# moth_v3_80mm_main_board.net
KiCad netlist of a schematic drawn in EAGLE
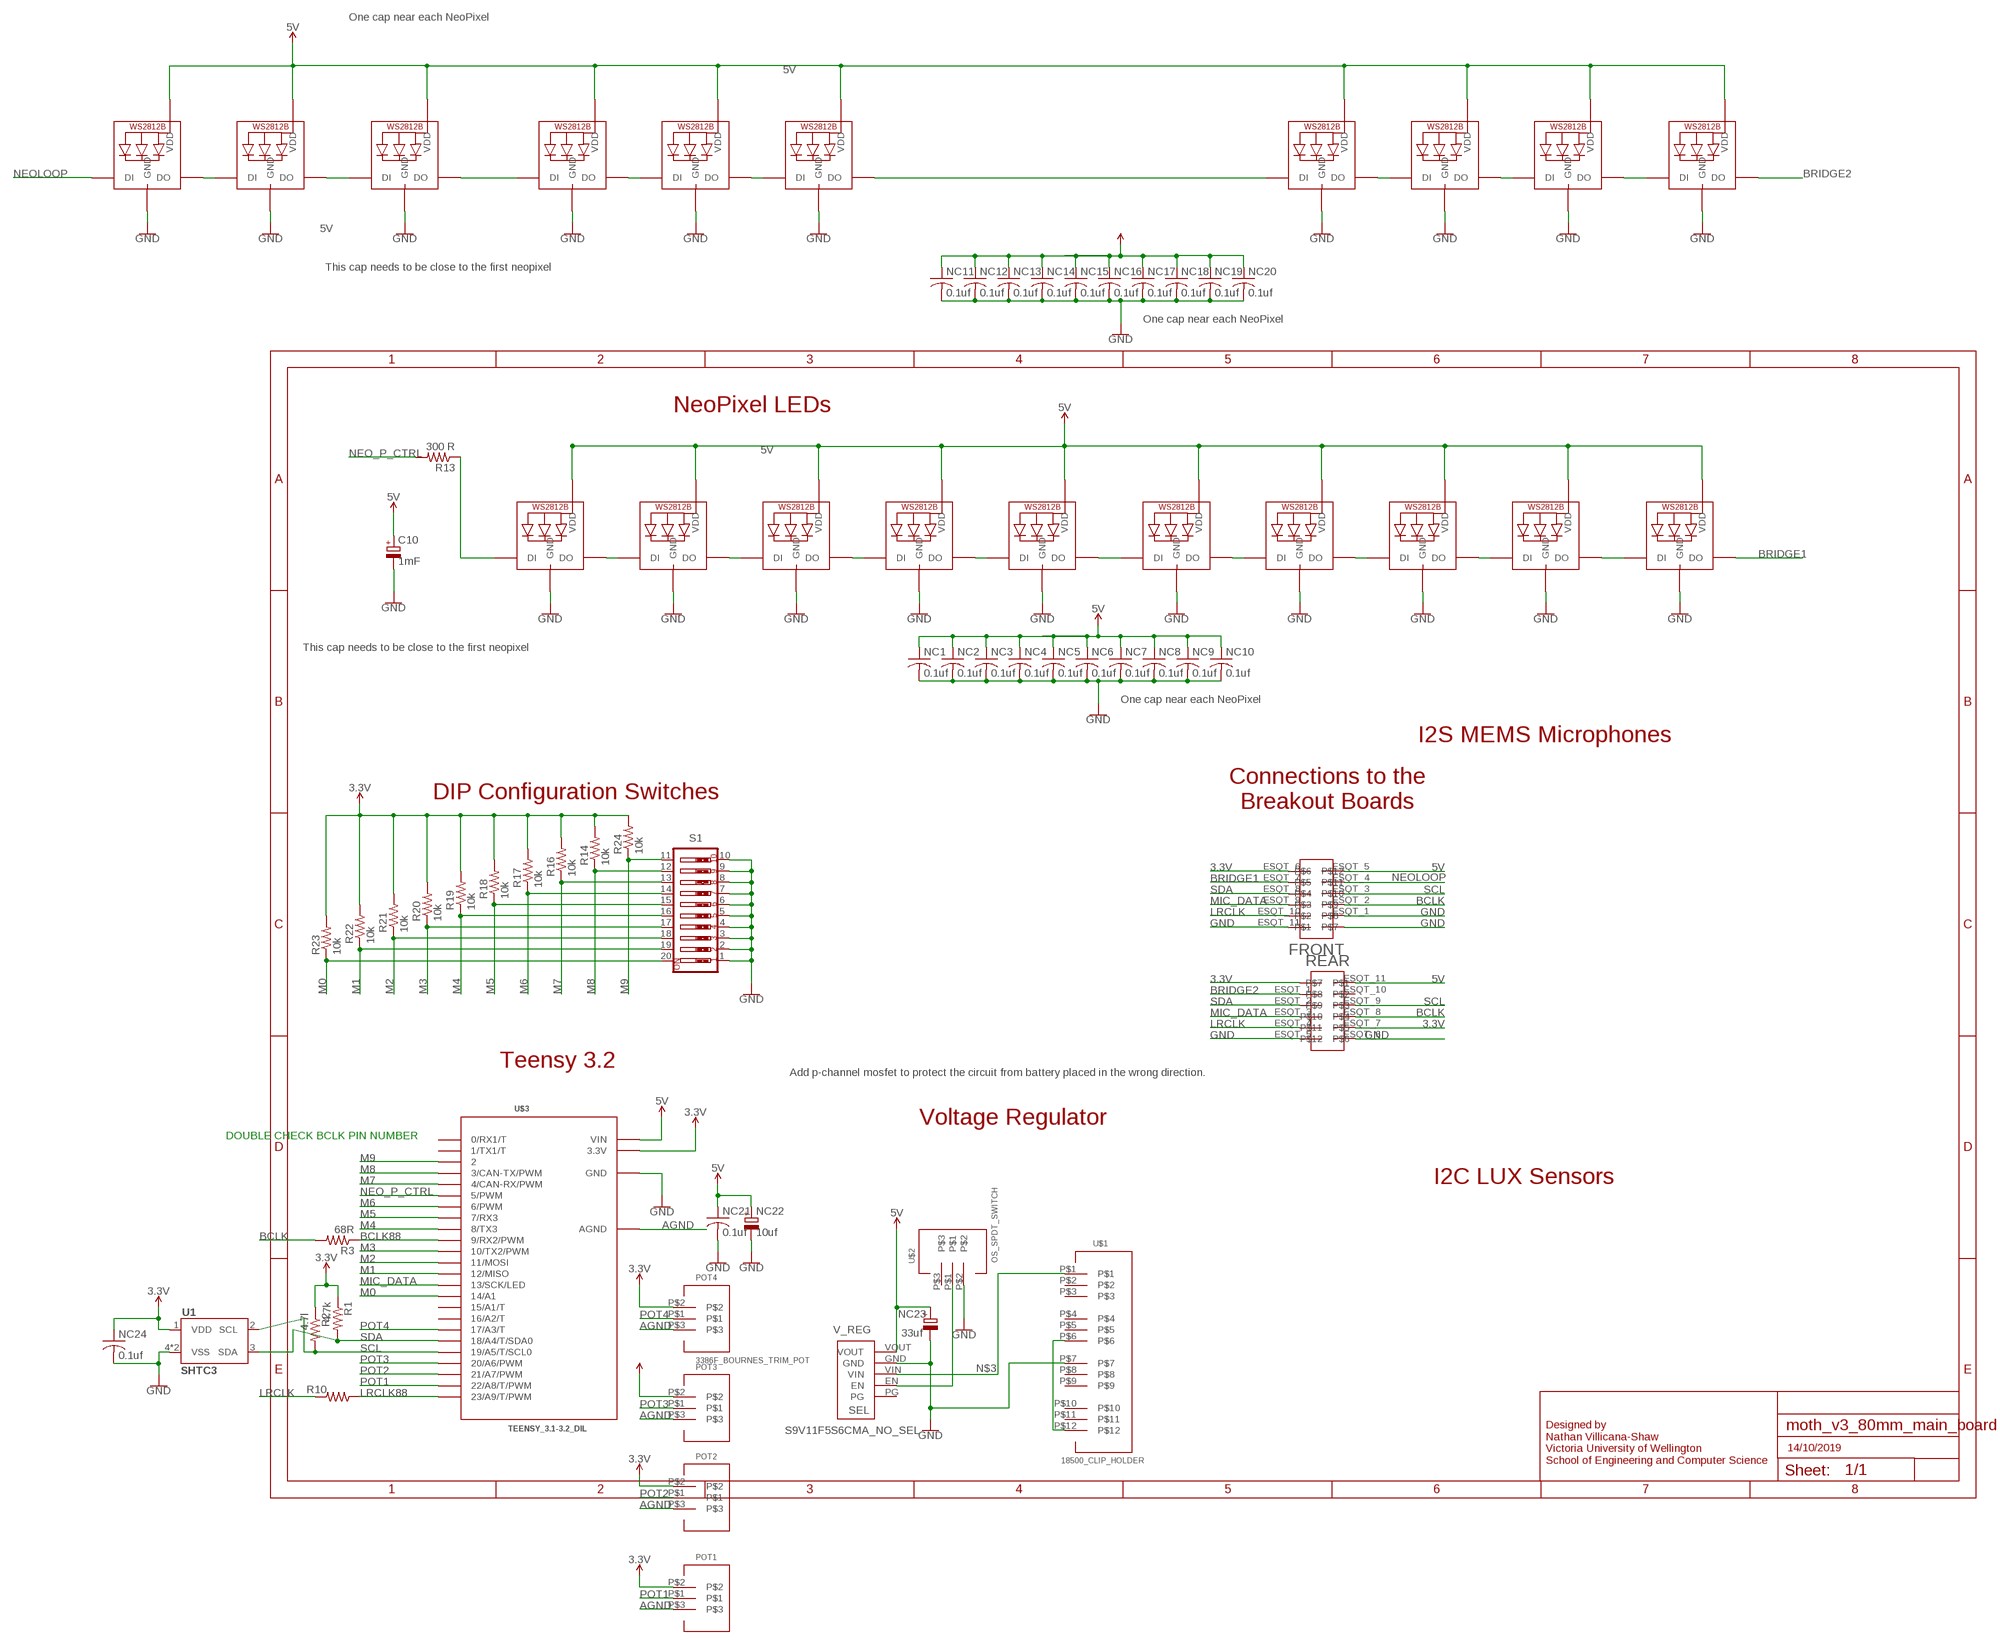
[diagram p0: schematic, sheet 1]

(export (version "E")
  (design (tool "Eeschema 10.0.6"))
  (components
    (comp (ref "C10")
      (value "1mF")
      (footprint "eagle-import:153CLV-1010")
      (libsource (lib "eagle-import") (part "CPOL-EU153CLV-1010"))
    )
    (comp (ref "FRONT")
      (value "SAMTEC_ESQT_2X6_THROUGH_HOLE")
      (footprint "eagle-import:SAMTEC_ESQT_2X6_THROUGH_HOLE")
      (libsource (lib "eagle-import") (part "SAMTEC_ESQT_2X6_THROUGH_HOLE"))
    )
    (comp (ref "NC1")
      (value "0.1uf")
      (footprint "eagle-import:C0805K")
      (libsource (lib "eagle-import") (part "C-USC0805K"))
    )
    (comp (ref "NC2")
      (value "0.1uf")
      (footprint "eagle-import:C0805K")
      (libsource (lib "eagle-import") (part "C-USC0805K"))
    )
    (comp (ref "NC3")
      (value "0.1uf")
      (footprint "eagle-import:C0805K")
      (libsource (lib "eagle-import") (part "C-USC0805K"))
    )
    (comp (ref "NC4")
      (value "0.1uf")
      (footprint "eagle-import:C0805K")
      (libsource (lib "eagle-import") (part "C-USC0805K"))
    )
    (comp (ref "NC5")
      (value "0.1uf")
      (footprint "eagle-import:C0805K")
      (libsource (lib "eagle-import") (part "C-USC0805K"))
    )
    (comp (ref "NC6")
      (value "0.1uf")
      (footprint "eagle-import:C0805K")
      (libsource (lib "eagle-import") (part "C-USC0805K"))
    )
    (comp (ref "NC7")
      (value "0.1uf")
      (footprint "eagle-import:C0805K")
      (libsource (lib "eagle-import") (part "C-USC0805K"))
    )
    (comp (ref "NC8")
      (value "0.1uf")
      (footprint "eagle-import:C0805K")
      (libsource (lib "eagle-import") (part "C-USC0805K"))
    )
    (comp (ref "NC9")
      (value "0.1uf")
      (footprint "eagle-import:C0805K")
      (libsource (lib "eagle-import") (part "C-USC0805K"))
    )
    (comp (ref "NC10")
      (value "0.1uf")
      (footprint "eagle-import:C0805K")
      (libsource (lib "eagle-import") (part "C-USC0805K"))
    )
    (comp (ref "NC11")
      (value "0.1uf")
      (footprint "eagle-import:C0805K")
      (libsource (lib "eagle-import") (part "C-USC0805K"))
    )
    (comp (ref "NC12")
      (value "0.1uf")
      (footprint "eagle-import:C0805K")
      (libsource (lib "eagle-import") (part "C-USC0805K"))
    )
    (comp (ref "NC13")
      (value "0.1uf")
      (footprint "eagle-import:C0805K")
      (libsource (lib "eagle-import") (part "C-USC0805K"))
    )
    (comp (ref "NC14")
      (value "0.1uf")
      (footprint "eagle-import:C0805K")
      (libsource (lib "eagle-import") (part "C-USC0805K"))
    )
    (comp (ref "NC15")
      (value "0.1uf")
      (footprint "eagle-import:C0805K")
      (libsource (lib "eagle-import") (part "C-USC0805K"))
    )
    (comp (ref "NC16")
      (value "0.1uf")
      (footprint "eagle-import:C0805K")
      (libsource (lib "eagle-import") (part "C-USC0805K"))
    )
    (comp (ref "NC17")
      (value "0.1uf")
      (footprint "eagle-import:C0805K")
      (libsource (lib "eagle-import") (part "C-USC0805K"))
    )
    (comp (ref "NC18")
      (value "0.1uf")
      (footprint "eagle-import:C0805K")
      (libsource (lib "eagle-import") (part "C-USC0805K"))
    )
    (comp (ref "NC19")
      (value "0.1uf")
      (footprint "eagle-import:C0805K")
      (libsource (lib "eagle-import") (part "C-USC0805K"))
    )
    (comp (ref "NC20")
      (value "0.1uf")
      (footprint "eagle-import:C0805K")
      (libsource (lib "eagle-import") (part "C-USC0805K"))
    )
    (comp (ref "NC21")
      (value "0.1uf")
      (footprint "eagle-import:C0805K")
      (libsource (lib "eagle-import") (part "C-USC0805K"))
    )
    (comp (ref "NC22")
      (value "10uf")
      (footprint "eagle-import:E2,5-7")
      (libsource (lib "eagle-import") (part "CPOL-EUE2.5-7"))
    )
    (comp (ref "NC23")
      (value "33uf")
      (footprint "eagle-import:E2,5-7")
      (libsource (lib "eagle-import") (part "CPOL-EUE2.5-7"))
    )
    (comp (ref "NC24")
      (value "0.1uf")
      (footprint "eagle-import:C0805K")
      (libsource (lib "eagle-import") (part "C-USC0805K"))
    )
    (comp (ref "NEO1")
      (value "WS2812B5050")
      (footprint "eagle-import:WS2812B")
      (libsource (lib "eagle-import") (part "WS2812B5050"))
    )
    (comp (ref "NEO2")
      (value "WS2812B5050")
      (footprint "eagle-import:WS2812B")
      (libsource (lib "eagle-import") (part "WS2812B5050"))
    )
    (comp (ref "NEO3")
      (value "WS2812B5050")
      (footprint "eagle-import:WS2812B")
      (libsource (lib "eagle-import") (part "WS2812B5050"))
    )
    (comp (ref "NEO4")
      (value "WS2812B5050")
      (footprint "eagle-import:WS2812B")
      (libsource (lib "eagle-import") (part "WS2812B5050"))
    )
    (comp (ref "NEO5")
      (value "WS2812B5050")
      (footprint "eagle-import:WS2812B")
      (libsource (lib "eagle-import") (part "WS2812B5050"))
    )
    (comp (ref "NEO6")
      (value "WS2812B5050")
      (footprint "eagle-import:WS2812B")
      (libsource (lib "eagle-import") (part "WS2812B5050"))
    )
    (comp (ref "NEO7")
      (value "WS2812B5050")
      (footprint "eagle-import:WS2812B")
      (libsource (lib "eagle-import") (part "WS2812B5050"))
    )
    (comp (ref "NEO8")
      (value "WS2812B5050")
      (footprint "eagle-import:WS2812B")
      (libsource (lib "eagle-import") (part "WS2812B5050"))
    )
    (comp (ref "NEO9")
      (value "WS2812B5050")
      (footprint "eagle-import:WS2812B")
      (libsource (lib "eagle-import") (part "WS2812B5050"))
    )
    (comp (ref "NEO10")
      (value "WS2812B5050")
      (footprint "eagle-import:WS2812B")
      (libsource (lib "eagle-import") (part "WS2812B5050"))
    )
    (comp (ref "NEO11")
      (value "WS2812B5050")
      (footprint "eagle-import:WS2812B")
      (libsource (lib "eagle-import") (part "WS2812B5050"))
    )
    (comp (ref "NEO12")
      (value "WS2812B5050")
      (footprint "eagle-import:WS2812B")
      (libsource (lib "eagle-import") (part "WS2812B5050"))
    )
    (comp (ref "NEO13")
      (value "WS2812B5050")
      (footprint "eagle-import:WS2812B")
      (libsource (lib "eagle-import") (part "WS2812B5050"))
    )
    (comp (ref "NEO14")
      (value "WS2812B5050")
      (footprint "eagle-import:WS2812B")
      (libsource (lib "eagle-import") (part "WS2812B5050"))
    )
    (comp (ref "NEO15")
      (value "WS2812B5050")
      (footprint "eagle-import:WS2812B")
      (libsource (lib "eagle-import") (part "WS2812B5050"))
    )
    (comp (ref "NEO16")
      (value "WS2812B5050")
      (footprint "eagle-import:WS2812B")
      (libsource (lib "eagle-import") (part "WS2812B5050"))
    )
    (comp (ref "NEO17")
      (value "WS2812B5050")
      (footprint "eagle-import:WS2812B")
      (libsource (lib "eagle-import") (part "WS2812B5050"))
    )
    (comp (ref "NEO18")
      (value "WS2812B5050")
      (footprint "eagle-import:WS2812B")
      (libsource (lib "eagle-import") (part "WS2812B5050"))
    )
    (comp (ref "NEO19")
      (value "WS2812B5050")
      (footprint "eagle-import:WS2812B")
      (libsource (lib "eagle-import") (part "WS2812B5050"))
    )
    (comp (ref "NEO20")
      (value "WS2812B5050")
      (footprint "eagle-import:WS2812B")
      (libsource (lib "eagle-import") (part "WS2812B5050"))
    )
    (comp (ref "POT1")
      (value "3386F_BOURNES_TRIM_POT")
      (footprint "eagle-import:3386_BOURNS_TRIM_POT")
      (libsource (lib "eagle-import") (part "3386F_BOURNES_TRIM_POT"))
    )
    (comp (ref "POT2")
      (value "3386F_BOURNES_TRIM_POT")
      (footprint "eagle-import:3386_BOURNS_TRIM_POT")
      (libsource (lib "eagle-import") (part "3386F_BOURNES_TRIM_POT"))
    )
    (comp (ref "POT3")
      (value "3386F_BOURNES_TRIM_POT")
      (footprint "eagle-import:3386_BOURNS_TRIM_POT")
      (libsource (lib "eagle-import") (part "3386F_BOURNES_TRIM_POT"))
    )
    (comp (ref "POT4")
      (value "3386F_BOURNES_TRIM_POT")
      (footprint "eagle-import:3386_BOURNS_TRIM_POT")
      (libsource (lib "eagle-import") (part "3386F_BOURNES_TRIM_POT"))
    )
    (comp (ref "R1")
      (value "4.7k")
      (footprint "eagle-import:R0805")
      (libsource (lib "eagle-import") (part "R-US_R0805"))
    )
    (comp (ref "R2")
      (value "4.7l")
      (footprint "eagle-import:R0805")
      (libsource (lib "eagle-import") (part "R-US_R0805"))
    )
    (comp (ref "R3")
      (value "68R")
      (footprint "eagle-import:R0805")
      (libsource (lib "eagle-import") (part "R-US_R0805"))
    )
    (comp (ref "R10")
      (value "68R")
      (footprint "eagle-import:R0805")
      (libsource (lib "eagle-import") (part "R-US_R0805"))
    )
    (comp (ref "R13")
      (value "300 R")
      (footprint "eagle-import:R0805")
      (libsource (lib "eagle-import") (part "R-US_R0805"))
    )
    (comp (ref "R14")
      (value "10k")
      (footprint "eagle-import:R0805")
      (libsource (lib "eagle-import") (part "R-US_R0805"))
    )
    (comp (ref "R16")
      (value "10k")
      (footprint "eagle-import:R0805")
      (libsource (lib "eagle-import") (part "R-US_R0805"))
    )
    (comp (ref "R17")
      (value "10k")
      (footprint "eagle-import:R0805")
      (libsource (lib "eagle-import") (part "R-US_R0805"))
    )
    (comp (ref "R18")
      (value "10k")
      (footprint "eagle-import:R0805")
      (libsource (lib "eagle-import") (part "R-US_R0805"))
    )
    (comp (ref "R19")
      (value "10k")
      (footprint "eagle-import:R0805")
      (libsource (lib "eagle-import") (part "R-US_R0805"))
    )
    (comp (ref "R20")
      (value "10k")
      (footprint "eagle-import:R0805")
      (libsource (lib "eagle-import") (part "R-US_R0805"))
    )
    (comp (ref "R21")
      (value "10k")
      (footprint "eagle-import:R0805")
      (libsource (lib "eagle-import") (part "R-US_R0805"))
    )
    (comp (ref "R22")
      (value "10k")
      (footprint "eagle-import:R0805")
      (libsource (lib "eagle-import") (part "R-US_R0805"))
    )
    (comp (ref "R23")
      (value "10k")
      (footprint "eagle-import:M0805")
      (libsource (lib "eagle-import") (part "R-US_M0805"))
    )
    (comp (ref "R24")
      (value "10k")
      (footprint "eagle-import:R0805")
      (libsource (lib "eagle-import") (part "R-US_R0805"))
    )
    (comp (ref "REAR")
      (value "SAMTEC_ESQT_2X6_THROUGH_HOLE")
      (footprint "eagle-import:SAMTEC_ESQT_2X6_THROUGH_HOLE")
      (libsource (lib "eagle-import") (part "SAMTEC_ESQT_2X6_THROUGH_HOLE"))
    )
    (comp (ref "S1")
      (value "SW_DIP-10")
      (footprint "eagle-import:EDG-10")
      (libsource (lib "eagle-import") (part "SW_DIP-10"))
    )
    (comp (ref "U$1")
      (value "18500_CLIP_HOLDER")
      (footprint "eagle-import:3PINBATTERY_CLIP")
      (fields (field (name "SPICEPREFIX") "X"))
      (libsource (lib "eagle-import") (part "18500_CLIP_HOLDER"))
    )
    (comp (ref "U$2")
      (value "OS_SPDT_SWITCH")
      (footprint "eagle-import:OS_SPDT_SLIDE_SWITCH")
      (libsource (lib "eagle-import") (part "OS_SPDT_SWITCH"))
    )
    (comp (ref "U$3")
      (value "TEENSY_3.1-3.2_DIL")
      (footprint "eagle-import:TEENSY_3.0-3.2&LC_DIL")
      (libsource (lib "eagle-import") (part "TEENSY_3.1-3.2_DIL"))
    )
    (comp (ref "U1")
      (value "SHTC3")
      (footprint "eagle-import:SHTC3")
      (libsource (lib "eagle-import") (part "SHTC3"))
    )
    (comp (ref "V_REG")
      (value "S9V11F5S6CMA_NO_SEL")
      (footprint "eagle-import:S9V11F3S5CMA_NO_SEL")
      (libsource (lib "eagle-import") (part "S9V11F5S6CMA_NO_SEL"))
    )
  )
  (nets
    (net (code "1") (name "/AGND") (class "Default")
      (node (ref "POT1") (pin "P$3") (pinfunction "P$3_P$3") (pintype "bidirectional"))
      (node (ref "POT2") (pin "P$3") (pinfunction "P$3_P$3") (pintype "bidirectional"))
      (node (ref "POT3") (pin "P$3") (pinfunction "P$3_P$3") (pintype "bidirectional"))
      (node (ref "POT4") (pin "P$3") (pinfunction "P$3_P$3") (pintype "bidirectional"))
      (node (ref "U$3") (pin "AGND") (pinfunction "AGND_AGND") (pintype "power_in"))
    )
    (net (code "2") (name "/BCLK") (class "Default")
      (node (ref "FRONT") (pin "ESQT_2") (pinfunction "P$3_ESQT_2") (pintype "bidirectional"))
      (node (ref "R3") (pin "2") (pinfunction "2_2") (pintype "passive"))
      (node (ref "REAR") (pin "ESQT_8") (pinfunction "P$10_ESQT_8") (pintype "bidirectional"))
    )
    (net (code "3") (name "/BCLK88") (class "Default")
      (node (ref "R3") (pin "1") (pinfunction "1_1") (pintype "passive"))
      (node (ref "U$3") (pin "9") (pinfunction "9/RX2/PWM_9") (pintype "bidirectional"))
    )
    (net (code "4") (name "/BRIDGE1") (class "Default")
      (node (ref "FRONT") (pin "ESQT_7") (pinfunction "P$11_ESQT_7") (pintype "bidirectional"))
      (node (ref "NEO10") (pin "2-DOUT") (pinfunction "DO_2-DOUT") (pintype "output"))
    )
    (net (code "5") (name "/BRIDGE2") (class "Default")
      (node (ref "NEO20") (pin "2-DOUT") (pinfunction "DO_2-DOUT") (pintype "output"))
      (node (ref "REAR") (pin "ESQT_1") (pinfunction "P$2_ESQT_1") (pintype "bidirectional"))
    )
    (net (code "6") (name "/LRCLK") (class "Default")
      (node (ref "FRONT") (pin "ESQT_10") (pinfunction "P$8_ESQT_10") (pintype "bidirectional"))
      (node (ref "R10") (pin "2") (pinfunction "2_2") (pintype "passive"))
      (node (ref "REAR") (pin "ESQT_4") (pinfunction "P$5_ESQT_4") (pintype "bidirectional"))
    )
    (net (code "7") (name "/LRCLK88") (class "Default")
      (node (ref "R10") (pin "1") (pinfunction "1_1") (pintype "passive"))
      (node (ref "U$3") (pin "23/A9") (pinfunction "23/A9/T/PWM_23/A9") (pintype "bidirectional"))
    )
    (net (code "8") (name "/M0") (class "Default")
      (node (ref "R23") (pin "1") (pinfunction "1_1") (pintype "passive"))
      (node (ref "S1") (pin "20") (pinfunction "20_20") (pintype "passive"))
      (node (ref "U$3") (pin "14/A0") (pinfunction "14/A1_14/A0") (pintype "bidirectional"))
    )
    (net (code "9") (name "/M1") (class "Default")
      (node (ref "R22") (pin "1") (pinfunction "1_1") (pintype "passive"))
      (node (ref "S1") (pin "19") (pinfunction "19_19") (pintype "passive"))
      (node (ref "U$3") (pin "12") (pinfunction "12/MISO_12") (pintype "bidirectional"))
    )
    (net (code "10") (name "/M2") (class "Default")
      (node (ref "R21") (pin "1") (pinfunction "1_1") (pintype "passive"))
      (node (ref "S1") (pin "18") (pinfunction "18_18") (pintype "passive"))
      (node (ref "U$3") (pin "11") (pinfunction "11/MOSI_11") (pintype "bidirectional"))
    )
    (net (code "11") (name "/M3") (class "Default")
      (node (ref "R20") (pin "1") (pinfunction "1_1") (pintype "passive"))
      (node (ref "S1") (pin "17") (pinfunction "17_17") (pintype "passive"))
      (node (ref "U$3") (pin "10") (pinfunction "10/TX2/PWM_10") (pintype "bidirectional"))
    )
    (net (code "12") (name "/M4") (class "Default")
      (node (ref "R19") (pin "1") (pinfunction "1_1") (pintype "passive"))
      (node (ref "S1") (pin "16") (pinfunction "16_16") (pintype "passive"))
      (node (ref "U$3") (pin "8") (pinfunction "8/TX3_8") (pintype "bidirectional"))
    )
    (net (code "13") (name "/M5") (class "Default")
      (node (ref "R18") (pin "1") (pinfunction "1_1") (pintype "passive"))
      (node (ref "S1") (pin "15") (pinfunction "15_15") (pintype "passive"))
      (node (ref "U$3") (pin "7") (pinfunction "7/RX3_7") (pintype "bidirectional"))
    )
    (net (code "14") (name "/M6") (class "Default")
      (node (ref "R17") (pin "1") (pinfunction "1_1") (pintype "passive"))
      (node (ref "S1") (pin "14") (pinfunction "14_14") (pintype "passive"))
      (node (ref "U$3") (pin "6") (pinfunction "6/PWM_6") (pintype "bidirectional"))
    )
    (net (code "15") (name "/M7") (class "Default")
      (node (ref "R16") (pin "1") (pinfunction "1_1") (pintype "passive"))
      (node (ref "S1") (pin "13") (pinfunction "13_13") (pintype "passive"))
      (node (ref "U$3") (pin "4") (pinfunction "4/CAN-RX/PWM_4") (pintype "bidirectional"))
    )
    (net (code "16") (name "/M8") (class "Default")
      (node (ref "R14") (pin "1") (pinfunction "1_1") (pintype "passive"))
      (node (ref "S1") (pin "12") (pinfunction "12_12") (pintype "passive"))
      (node (ref "U$3") (pin "3") (pinfunction "3/CAN-TX/PWM_3") (pintype "bidirectional"))
    )
    (net (code "17") (name "/M9") (class "Default")
      (node (ref "R24") (pin "1") (pinfunction "1_1") (pintype "passive"))
      (node (ref "S1") (pin "11") (pinfunction "11_11") (pintype "passive"))
      (node (ref "U$3") (pin "2") (pinfunction "2_2") (pintype "bidirectional"))
    )
    (net (code "18") (name "/MIC_DATA") (class "Default")
      (node (ref "FRONT") (pin "ESQT_9") (pinfunction "P$9_ESQT_9") (pintype "bidirectional"))
      (node (ref "REAR") (pin "ESQT_3") (pinfunction "P$4_ESQT_3") (pintype "bidirectional"))
      (node (ref "U$3") (pin "13") (pinfunction "13/SCK/LED_13") (pintype "bidirectional"))
    )
    (net (code "19") (name "/N$3") (class "Default")
      (node (ref "U$1") (pin "P$1") (pinfunction "P$1_P$1") (pintype "bidirectional"))
      (node (ref "V_REG") (pin "VIN") (pinfunction "VIN_VIN") (pintype "bidirectional"))
    )
    (net (code "20") (name "/NEOLOOP") (class "Default")
      (node (ref "FRONT") (pin "ESQT_4") (pinfunction "P$5_ESQT_4") (pintype "bidirectional"))
      (node (ref "NEO11") (pin "4-DIN") (pinfunction "DI_4-DIN") (pintype "input"))
    )
    (net (code "21") (name "/NEO_P_CTRL") (class "Default")
      (node (ref "R13") (pin "2") (pinfunction "2_2") (pintype "passive"))
      (node (ref "U$3") (pin "5") (pinfunction "5/PWM_5") (pintype "bidirectional"))
    )
    (net (code "22") (name "/POT1") (class "Default")
      (node (ref "POT1") (pin "P$1") (pinfunction "P$1_P$1") (pintype "bidirectional"))
      (node (ref "U$3") (pin "22/A8") (pinfunction "22/A8/T/PWM_22/A8") (pintype "bidirectional"))
    )
    (net (code "23") (name "/POT2") (class "Default")
      (node (ref "POT2") (pin "P$1") (pinfunction "P$1_P$1") (pintype "bidirectional"))
      (node (ref "U$3") (pin "21/A7") (pinfunction "21/A7/PWM_21/A7") (pintype "bidirectional"))
    )
    (net (code "24") (name "/POT3") (class "Default")
      (node (ref "POT3") (pin "P$1") (pinfunction "P$1_P$1") (pintype "bidirectional"))
      (node (ref "U$3") (pin "20/A6") (pinfunction "20/A6/PWM_20/A6") (pintype "bidirectional"))
    )
    (net (code "25") (name "/POT4") (class "Default")
      (node (ref "POT4") (pin "P$1") (pinfunction "P$1_P$1") (pintype "bidirectional"))
      (node (ref "U$3") (pin "17/A3") (pinfunction "17/A3/T_17/A3") (pintype "bidirectional"))
    )
    (net (code "26") (name "/SCL") (class "Default")
      (node (ref "FRONT") (pin "ESQT_3") (pinfunction "P$4_ESQT_3") (pintype "bidirectional"))
      (node (ref "R2") (pin "2") (pinfunction "2_2") (pintype "passive"))
      (node (ref "REAR") (pin "ESQT_9") (pinfunction "P$9_ESQT_9") (pintype "bidirectional"))
      (node (ref "U$3") (pin "19/A5") (pinfunction "19/A5/T/SCL0_19/A5") (pintype "bidirectional"))
      (node (ref "U1") (pin "2") (pinfunction "SCL_2") (pintype "bidirectional"))
    )
    (net (code "27") (name "/SDA") (class "Default")
      (node (ref "FRONT") (pin "ESQT_8") (pinfunction "P$10_ESQT_8") (pintype "bidirectional"))
      (node (ref "R1") (pin "2") (pinfunction "2_2") (pintype "passive"))
      (node (ref "REAR") (pin "ESQT_2") (pinfunction "P$3_ESQT_2") (pintype "bidirectional"))
      (node (ref "U$3") (pin "18/A4") (pinfunction "18/A4/T/SDA0_18/A4") (pintype "bidirectional"))
      (node (ref "U1") (pin "3") (pinfunction "SDA_3") (pintype "bidirectional"))
    )
    (net (code "28") (name "3.3V") (class "Default")
      (node (ref "FRONT") (pin "ESQT_6") (pinfunction "P$12_ESQT_6") (pintype "bidirectional"))
      (node (ref "NC24") (pin "1") (pinfunction "1_1") (pintype "passive"))
      (node (ref "POT1") (pin "P$2") (pinfunction "P$2_P$2") (pintype "bidirectional"))
      (node (ref "POT2") (pin "P$2") (pinfunction "P$2_P$2") (pintype "bidirectional"))
      (node (ref "POT3") (pin "P$2") (pinfunction "P$2_P$2") (pintype "bidirectional"))
      (node (ref "POT4") (pin "P$2") (pinfunction "P$2_P$2") (pintype "bidirectional"))
      (node (ref "R1") (pin "1") (pinfunction "1_1") (pintype "passive"))
      (node (ref "R14") (pin "2") (pinfunction "2_2") (pintype "passive"))
      (node (ref "R16") (pin "2") (pinfunction "2_2") (pintype "passive"))
      (node (ref "R17") (pin "2") (pinfunction "2_2") (pintype "passive"))
      (node (ref "R18") (pin "2") (pinfunction "2_2") (pintype "passive"))
      (node (ref "R19") (pin "2") (pinfunction "2_2") (pintype "passive"))
      (node (ref "R2") (pin "1") (pinfunction "1_1") (pintype "passive"))
      (node (ref "R20") (pin "2") (pinfunction "2_2") (pintype "passive"))
      (node (ref "R21") (pin "2") (pinfunction "2_2") (pintype "passive"))
      (node (ref "R22") (pin "2") (pinfunction "2_2") (pintype "passive"))
      (node (ref "R23") (pin "2") (pinfunction "2_2") (pintype "passive"))
      (node (ref "R24") (pin "2") (pinfunction "2_2") (pintype "passive"))
      (node (ref "REAR") (pin "ESQT_0") (pinfunction "P$1_ESQT_0") (pintype "bidirectional"))
      (node (ref "REAR") (pin "ESQT_7") (pinfunction "P$11_ESQT_7") (pintype "bidirectional"))
      (node (ref "U$3") (pin "3.3V") (pinfunction "3.3V_3.3V") (pintype "power_in"))
      (node (ref "U1") (pin "1") (pinfunction "VDD_1") (pintype "bidirectional"))
    )
    (net (code "29") (name "5V") (class "Default")
      (node (ref "C10") (pin "+") (pinfunction "+_+") (pintype "passive"))
      (node (ref "FRONT") (pin "ESQT_5") (pinfunction "P$6_ESQT_5") (pintype "bidirectional"))
      (node (ref "NC1") (pin "1") (pinfunction "1_1") (pintype "passive"))
      (node (ref "NC10") (pin "1") (pinfunction "1_1") (pintype "passive"))
      (node (ref "NC11") (pin "1") (pinfunction "1_1") (pintype "passive"))
      (node (ref "NC12") (pin "1") (pinfunction "1_1") (pintype "passive"))
      (node (ref "NC13") (pin "1") (pinfunction "1_1") (pintype "passive"))
      (node (ref "NC14") (pin "1") (pinfunction "1_1") (pintype "passive"))
      (node (ref "NC15") (pin "1") (pinfunction "1_1") (pintype "passive"))
      (node (ref "NC16") (pin "1") (pinfunction "1_1") (pintype "passive"))
      (node (ref "NC17") (pin "1") (pinfunction "1_1") (pintype "passive"))
      (node (ref "NC18") (pin "1") (pinfunction "1_1") (pintype "passive"))
      (node (ref "NC19") (pin "1") (pinfunction "1_1") (pintype "passive"))
      (node (ref "NC2") (pin "1") (pinfunction "1_1") (pintype "passive"))
      (node (ref "NC20") (pin "1") (pinfunction "1_1") (pintype "passive"))
      (node (ref "NC21") (pin "1") (pinfunction "1_1") (pintype "passive"))
      (node (ref "NC22") (pin "+") (pinfunction "+_+") (pintype "passive"))
      (node (ref "NC23") (pin "+") (pinfunction "+_+") (pintype "passive"))
      (node (ref "NC3") (pin "1") (pinfunction "1_1") (pintype "passive"))
      (node (ref "NC4") (pin "1") (pinfunction "1_1") (pintype "passive"))
      (node (ref "NC5") (pin "1") (pinfunction "1_1") (pintype "passive"))
      (node (ref "NC6") (pin "1") (pinfunction "1_1") (pintype "passive"))
      (node (ref "NC7") (pin "1") (pinfunction "1_1") (pintype "passive"))
      (node (ref "NC8") (pin "1") (pinfunction "1_1") (pintype "passive"))
      (node (ref "NC9") (pin "1") (pinfunction "1_1") (pintype "passive"))
      (node (ref "NEO1") (pin "1-VDD") (pinfunction "VDD_1-VDD") (pintype "power_in"))
      (node (ref "NEO10") (pin "1-VDD") (pinfunction "VDD_1-VDD") (pintype "power_in"))
      (node (ref "NEO11") (pin "1-VDD") (pinfunction "VDD_1-VDD") (pintype "power_in"))
      (node (ref "NEO12") (pin "1-VDD") (pinfunction "VDD_1-VDD") (pintype "power_in"))
      (node (ref "NEO13") (pin "1-VDD") (pinfunction "VDD_1-VDD") (pintype "power_in"))
      (node (ref "NEO14") (pin "1-VDD") (pinfunction "VDD_1-VDD") (pintype "power_in"))
      (node (ref "NEO15") (pin "1-VDD") (pinfunction "VDD_1-VDD") (pintype "power_in"))
      (node (ref "NEO16") (pin "1-VDD") (pinfunction "VDD_1-VDD") (pintype "power_in"))
      (node (ref "NEO17") (pin "1-VDD") (pinfunction "VDD_1-VDD") (pintype "power_in"))
      (node (ref "NEO18") (pin "1-VDD") (pinfunction "VDD_1-VDD") (pintype "power_in"))
      (node (ref "NEO19") (pin "1-VDD") (pinfunction "VDD_1-VDD") (pintype "power_in"))
      (node (ref "NEO2") (pin "1-VDD") (pinfunction "VDD_1-VDD") (pintype "power_in"))
      (node (ref "NEO20") (pin "1-VDD") (pinfunction "VDD_1-VDD") (pintype "power_in"))
      (node (ref "NEO3") (pin "1-VDD") (pinfunction "VDD_1-VDD") (pintype "power_in"))
      (node (ref "NEO4") (pin "1-VDD") (pinfunction "VDD_1-VDD") (pintype "power_in"))
      (node (ref "NEO5") (pin "1-VDD") (pinfunction "VDD_1-VDD") (pintype "power_in"))
      (node (ref "NEO6") (pin "1-VDD") (pinfunction "VDD_1-VDD") (pintype "power_in"))
      (node (ref "NEO7") (pin "1-VDD") (pinfunction "VDD_1-VDD") (pintype "power_in"))
      (node (ref "NEO8") (pin "1-VDD") (pinfunction "VDD_1-VDD") (pintype "power_in"))
      (node (ref "NEO9") (pin "1-VDD") (pinfunction "VDD_1-VDD") (pintype "power_in"))
      (node (ref "REAR") (pin "ESQT_11") (pinfunction "P$7_ESQT_11") (pintype "bidirectional"))
      (node (ref "U$3") (pin "VIN") (pinfunction "VIN_VIN") (pintype "power_in"))
      (node (ref "V_REG") (pin "VOUT") (pinfunction "VOUT_VOUT") (pintype "bidirectional"))
    )
    (net (code "30") (name "GND") (class "Default")
      (node (ref "C10") (pin "-") (pinfunction "-_-") (pintype "passive"))
      (node (ref "FRONT") (pin "ESQT_0") (pinfunction "P$1_ESQT_0") (pintype "bidirectional"))
      (node (ref "FRONT") (pin "ESQT_1") (pinfunction "P$2_ESQT_1") (pintype "bidirectional"))
      (node (ref "FRONT") (pin "ESQT_11") (pinfunction "P$7_ESQT_11") (pintype "bidirectional"))
      (node (ref "NC1") (pin "2") (pinfunction "2_2") (pintype "passive"))
      (node (ref "NC10") (pin "2") (pinfunction "2_2") (pintype "passive"))
      (node (ref "NC11") (pin "2") (pinfunction "2_2") (pintype "passive"))
      (node (ref "NC12") (pin "2") (pinfunction "2_2") (pintype "passive"))
      (node (ref "NC13") (pin "2") (pinfunction "2_2") (pintype "passive"))
      (node (ref "NC14") (pin "2") (pinfunction "2_2") (pintype "passive"))
      (node (ref "NC15") (pin "2") (pinfunction "2_2") (pintype "passive"))
      (node (ref "NC16") (pin "2") (pinfunction "2_2") (pintype "passive"))
      (node (ref "NC17") (pin "2") (pinfunction "2_2") (pintype "passive"))
      (node (ref "NC18") (pin "2") (pinfunction "2_2") (pintype "passive"))
      (node (ref "NC19") (pin "2") (pinfunction "2_2") (pintype "passive"))
      (node (ref "NC2") (pin "2") (pinfunction "2_2") (pintype "passive"))
      (node (ref "NC20") (pin "2") (pinfunction "2_2") (pintype "passive"))
      (node (ref "NC21") (pin "2") (pinfunction "2_2") (pintype "passive"))
      (node (ref "NC22") (pin "-") (pinfunction "-_-") (pintype "passive"))
      (node (ref "NC23") (pin "-") (pinfunction "-_-") (pintype "passive"))
      (node (ref "NC24") (pin "2") (pinfunction "2_2") (pintype "passive"))
      (node (ref "NC3") (pin "2") (pinfunction "2_2") (pintype "passive"))
      (node (ref "NC4") (pin "2") (pinfunction "2_2") (pintype "passive"))
      (node (ref "NC5") (pin "2") (pinfunction "2_2") (pintype "passive"))
      (node (ref "NC6") (pin "2") (pinfunction "2_2") (pintype "passive"))
      (node (ref "NC7") (pin "2") (pinfunction "2_2") (pintype "passive"))
      (node (ref "NC8") (pin "2") (pinfunction "2_2") (pintype "passive"))
      (node (ref "NC9") (pin "2") (pinfunction "2_2") (pintype "passive"))
      (node (ref "NEO1") (pin "3-GND") (pinfunction "GND_3-GND") (pintype "power_in"))
      (node (ref "NEO10") (pin "3-GND") (pinfunction "GND_3-GND") (pintype "power_in"))
      (node (ref "NEO11") (pin "3-GND") (pinfunction "GND_3-GND") (pintype "power_in"))
      (node (ref "NEO12") (pin "3-GND") (pinfunction "GND_3-GND") (pintype "power_in"))
      (node (ref "NEO13") (pin "3-GND") (pinfunction "GND_3-GND") (pintype "power_in"))
      (node (ref "NEO14") (pin "3-GND") (pinfunction "GND_3-GND") (pintype "power_in"))
      (node (ref "NEO15") (pin "3-GND") (pinfunction "GND_3-GND") (pintype "power_in"))
      (node (ref "NEO16") (pin "3-GND") (pinfunction "GND_3-GND") (pintype "power_in"))
      (node (ref "NEO17") (pin "3-GND") (pinfunction "GND_3-GND") (pintype "power_in"))
      (node (ref "NEO18") (pin "3-GND") (pinfunction "GND_3-GND") (pintype "power_in"))
      (node (ref "NEO19") (pin "3-GND") (pinfunction "GND_3-GND") (pintype "power_in"))
      (node (ref "NEO2") (pin "3-GND") (pinfunction "GND_3-GND") (pintype "power_in"))
      (node (ref "NEO20") (pin "3-GND") (pinfunction "GND_3-GND") (pintype "power_in"))
      (node (ref "NEO3") (pin "3-GND") (pinfunction "GND_3-GND") (pintype "power_in"))
      (node (ref "NEO4") (pin "3-GND") (pinfunction "GND_3-GND") (pintype "power_in"))
      (node (ref "NEO5") (pin "3-GND") (pinfunction "GND_3-GND") (pintype "power_in"))
      (node (ref "NEO6") (pin "3-GND") (pinfunction "GND_3-GND") (pintype "power_in"))
      (node (ref "NEO7") (pin "3-GND") (pinfunction "GND_3-GND") (pintype "power_in"))
      (node (ref "NEO8") (pin "3-GND") (pinfunction "GND_3-GND") (pintype "power_in"))
      (node (ref "NEO9") (pin "3-GND") (pinfunction "GND_3-GND") (pintype "power_in"))
      (node (ref "REAR") (pin "ESQT_5") (pinfunction "P$6_ESQT_5") (pintype "bidirectional"))
      (node (ref "REAR") (pin "ESQT_6") (pinfunction "P$12_ESQT_6") (pintype "bidirectional"))
      (node (ref "S1") (pin "1") (pinfunction "1_1") (pintype "passive"))
      (node (ref "S1") (pin "10") (pinfunction "10_10") (pintype "passive"))
      (node (ref "S1") (pin "2") (pinfunction "2_2") (pintype "passive"))
      (node (ref "S1") (pin "3") (pinfunction "3_3") (pintype "passive"))
      (node (ref "S1") (pin "4") (pinfunction "4_4") (pintype "passive"))
      (node (ref "S1") (pin "5") (pinfunction "5_5") (pintype "passive"))
      (node (ref "S1") (pin "6") (pinfunction "6_6") (pintype "passive"))
      (node (ref "S1") (pin "7") (pinfunction "7_7") (pintype "passive"))
      (node (ref "S1") (pin "8") (pinfunction "8_8") (pintype "passive"))
      (node (ref "S1") (pin "9") (pinfunction "9_9") (pintype "passive"))
      (node (ref "U$1") (pin "P$7") (pinfunction "P$7_P$7") (pintype "bidirectional"))
      (node (ref "U$2") (pin "P$2") (pinfunction "P$2_P$2") (pintype "bidirectional"))
      (node (ref "U$3") (pin "GND") (pinfunction "GND_GND") (pintype "power_in"))
      (node (ref "U1") (pin "4") (pinfunction "VSS_4") (pintype "bidirectional"))
      (node (ref "U1") (pin "5") (pinfunction "VSS_5") (pintype "bidirectional"))
      (node (ref "V_REG") (pin "GND") (pinfunction "GND_GND") (pintype "bidirectional"))
    )
    (net (code "31") (name "Net-(NEO1-DI)") (class "Default")
      (node (ref "NEO1") (pin "4-DIN") (pinfunction "DI_4-DIN") (pintype "input"))
      (node (ref "R13") (pin "1") (pinfunction "1_1") (pintype "passive"))
    )
    (net (code "32") (name "Net-(NEO1-DO)") (class "Default")
      (node (ref "NEO1") (pin "2-DOUT") (pinfunction "DO_2-DOUT") (pintype "output"))
      (node (ref "NEO2") (pin "4-DIN") (pinfunction "DI_4-DIN") (pintype "input"))
    )
    (net (code "33") (name "Net-(NEO2-DO)") (class "Default")
      (node (ref "NEO2") (pin "2-DOUT") (pinfunction "DO_2-DOUT") (pintype "output"))
      (node (ref "NEO3") (pin "4-DIN") (pinfunction "DI_4-DIN") (pintype "input"))
    )
    (net (code "34") (name "Net-(NEO3-DO)") (class "Default")
      (node (ref "NEO3") (pin "2-DOUT") (pinfunction "DO_2-DOUT") (pintype "output"))
      (node (ref "NEO4") (pin "4-DIN") (pinfunction "DI_4-DIN") (pintype "input"))
    )
    (net (code "35") (name "Net-(NEO4-DO)") (class "Default")
      (node (ref "NEO4") (pin "2-DOUT") (pinfunction "DO_2-DOUT") (pintype "output"))
      (node (ref "NEO5") (pin "4-DIN") (pinfunction "DI_4-DIN") (pintype "input"))
    )
    (net (code "36") (name "Net-(NEO5-DO)") (class "Default")
      (node (ref "NEO5") (pin "2-DOUT") (pinfunction "DO_2-DOUT") (pintype "output"))
      (node (ref "NEO6") (pin "4-DIN") (pinfunction "DI_4-DIN") (pintype "input"))
    )
    (net (code "37") (name "Net-(NEO6-DO)") (class "Default")
      (node (ref "NEO6") (pin "2-DOUT") (pinfunction "DO_2-DOUT") (pintype "output"))
      (node (ref "NEO7") (pin "4-DIN") (pinfunction "DI_4-DIN") (pintype "input"))
    )
    (net (code "38") (name "Net-(NEO7-DO)") (class "Default")
      (node (ref "NEO7") (pin "2-DOUT") (pinfunction "DO_2-DOUT") (pintype "output"))
      (node (ref "NEO8") (pin "4-DIN") (pinfunction "DI_4-DIN") (pintype "input"))
    )
    (net (code "39") (name "Net-(NEO8-DO)") (class "Default")
      (node (ref "NEO8") (pin "2-DOUT") (pinfunction "DO_2-DOUT") (pintype "output"))
      (node (ref "NEO9") (pin "4-DIN") (pinfunction "DI_4-DIN") (pintype "input"))
    )
    (net (code "40") (name "Net-(NEO10-DI)") (class "Default")
      (node (ref "NEO10") (pin "4-DIN") (pinfunction "DI_4-DIN") (pintype "input"))
      (node (ref "NEO9") (pin "2-DOUT") (pinfunction "DO_2-DOUT") (pintype "output"))
    )
    (net (code "41") (name "Net-(NEO11-DO)") (class "Default")
      (node (ref "NEO11") (pin "2-DOUT") (pinfunction "DO_2-DOUT") (pintype "output"))
      (node (ref "NEO12") (pin "4-DIN") (pinfunction "DI_4-DIN") (pintype "input"))
    )
    (net (code "42") (name "Net-(NEO12-DO)") (class "Default")
      (node (ref "NEO12") (pin "2-DOUT") (pinfunction "DO_2-DOUT") (pintype "output"))
      (node (ref "NEO13") (pin "4-DIN") (pinfunction "DI_4-DIN") (pintype "input"))
    )
    (net (code "43") (name "Net-(NEO13-DO)") (class "Default")
      (node (ref "NEO13") (pin "2-DOUT") (pinfunction "DO_2-DOUT") (pintype "output"))
      (node (ref "NEO14") (pin "4-DIN") (pinfunction "DI_4-DIN") (pintype "input"))
    )
    (net (code "44") (name "Net-(NEO14-DO)") (class "Default")
      (node (ref "NEO14") (pin "2-DOUT") (pinfunction "DO_2-DOUT") (pintype "output"))
      (node (ref "NEO15") (pin "4-DIN") (pinfunction "DI_4-DIN") (pintype "input"))
    )
    (net (code "45") (name "Net-(NEO15-DO)") (class "Default")
      (node (ref "NEO15") (pin "2-DOUT") (pinfunction "DO_2-DOUT") (pintype "output"))
      (node (ref "NEO16") (pin "4-DIN") (pinfunction "DI_4-DIN") (pintype "input"))
    )
    (net (code "46") (name "Net-(NEO16-DO)") (class "Default")
      (node (ref "NEO16") (pin "2-DOUT") (pinfunction "DO_2-DOUT") (pintype "output"))
      (node (ref "NEO17") (pin "4-DIN") (pinfunction "DI_4-DIN") (pintype "input"))
    )
    (net (code "47") (name "Net-(NEO17-DO)") (class "Default")
      (node (ref "NEO17") (pin "2-DOUT") (pinfunction "DO_2-DOUT") (pintype "output"))
      (node (ref "NEO18") (pin "4-DIN") (pinfunction "DI_4-DIN") (pintype "input"))
    )
    (net (code "48") (name "Net-(NEO18-DO)") (class "Default")
      (node (ref "NEO18") (pin "2-DOUT") (pinfunction "DO_2-DOUT") (pintype "output"))
      (node (ref "NEO19") (pin "4-DIN") (pinfunction "DI_4-DIN") (pintype "input"))
    )
    (net (code "49") (name "Net-(NEO19-DO)") (class "Default")
      (node (ref "NEO19") (pin "2-DOUT") (pinfunction "DO_2-DOUT") (pintype "output"))
      (node (ref "NEO20") (pin "4-DIN") (pinfunction "DI_4-DIN") (pintype "input"))
    )
    (net (code "50") (name "Net-(U$1-PadP$12)") (class "Default")
      (node (ref "U$1") (pin "P$12") (pinfunction "P$12_P$12") (pintype "bidirectional"))
      (node (ref "U$1") (pin "P$6") (pinfunction "P$6_P$6") (pintype "bidirectional"))
    )
    (net (code "51") (name "Net-(U$2-PadP$1)") (class "Default")
      (node (ref "U$2") (pin "P$1") (pinfunction "P$1_P$1") (pintype "bidirectional"))
      (node (ref "V_REG") (pin "EN") (pinfunction "EN_EN") (pintype "bidirectional"))
    )
    (net (code "52") (name "unconnected-(REAR-P$8-PadESQT_10)") (class "Default")
      (node (ref "REAR") (pin "ESQT_10") (pinfunction "P$8_ESQT_10") (pintype "bidirectional"))
    )
    (net (code "53") (name "unconnected-(U$1-PadP$2)") (class "Default")
      (node (ref "U$1") (pin "P$2") (pinfunction "P$2_P$2") (pintype "bidirectional"))
    )
    (net (code "54") (name "unconnected-(U$1-PadP$3)") (class "Default")
      (node (ref "U$1") (pin "P$3") (pinfunction "P$3_P$3") (pintype "bidirectional"))
    )
    (net (code "55") (name "unconnected-(U$1-PadP$4)") (class "Default")
      (node (ref "U$1") (pin "P$4") (pinfunction "P$4_P$4") (pintype "bidirectional"))
    )
    (net (code "56") (name "unconnected-(U$1-PadP$5)") (class "Default")
      (node (ref "U$1") (pin "P$5") (pinfunction "P$5_P$5") (pintype "bidirectional"))
    )
    (net (code "57") (name "unconnected-(U$1-PadP$8)") (class "Default")
      (node (ref "U$1") (pin "P$8") (pinfunction "P$8_P$8") (pintype "bidirectional"))
    )
    (net (code "58") (name "unconnected-(U$1-PadP$9)") (class "Default")
      (node (ref "U$1") (pin "P$9") (pinfunction "P$9_P$9") (pintype "bidirectional"))
    )
    (net (code "59") (name "unconnected-(U$1-PadP$10)") (class "Default")
      (node (ref "U$1") (pin "P$10") (pinfunction "P$10_P$10") (pintype "bidirectional"))
    )
    (net (code "60") (name "unconnected-(U$1-PadP$11)") (class "Default")
      (node (ref "U$1") (pin "P$11") (pinfunction "P$11_P$11") (pintype "bidirectional"))
    )
    (net (code "61") (name "unconnected-(U$2-PadP$3)") (class "Default")
      (node (ref "U$2") (pin "P$3") (pinfunction "P$3_P$3") (pintype "bidirectional"))
    )
    (net (code "62") (name "unconnected-(U$3-0{slash}RX1{slash}T-Pad0)") (class "Default")
      (node (ref "U$3") (pin "0") (pinfunction "0/RX1/T_0") (pintype "bidirectional"))
    )
    (net (code "63") (name "unconnected-(U$3-1{slash}TX1{slash}T-Pad1)") (class "Default")
      (node (ref "U$3") (pin "1") (pinfunction "1/TX1/T_1") (pintype "bidirectional"))
    )
    (net (code "64") (name "unconnected-(U$3-15{slash}A1{slash}T-Pad15{slash}A1)") (class "Default")
      (node (ref "U$3") (pin "15/A1") (pinfunction "15/A1/T_15/A1") (pintype "bidirectional"))
    )
    (net (code "65") (name "unconnected-(U$3-16{slash}A2{slash}T-Pad16{slash}A2)") (class "Default")
      (node (ref "U$3") (pin "16/A2") (pinfunction "16/A2/T_16/A2") (pintype "bidirectional"))
    )
    (net (code "66") (name "unconnected-(V_REG-PadPG)") (class "Default")
      (node (ref "V_REG") (pin "PG") (pinfunction "PG_PG") (pintype "bidirectional"))
    )
  )
)
